# QCW_Bridge_PCBA.net
KiCad netlist of a schematic drawn in Altium Designer
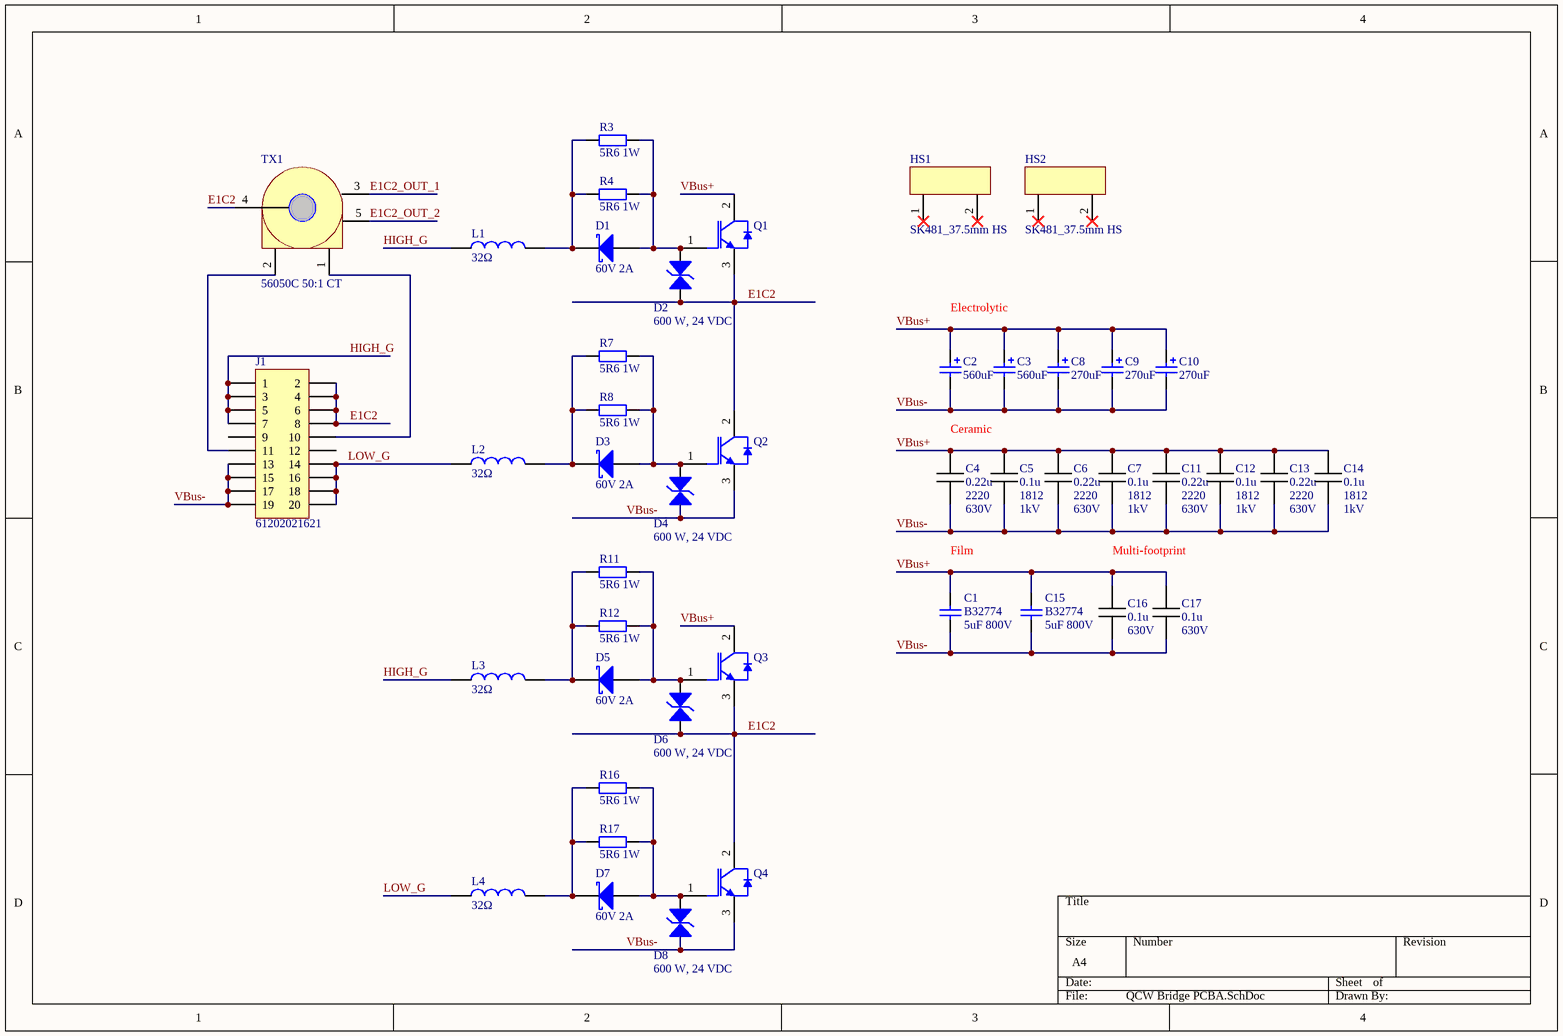
[diagram p0: QCW Bridge PCBA.SchDoc]

(export (version "E")
  (design (tool "Eeschema 10.0.6"))
  (components
    (comp (ref "C1")
      (value "B32774")
      (footprint "B32774 5uF 800V")
      (description "Capacitor")
      (fields (field (name "ALTIUM_VALUE") "5uF 800V") (field (name "PUBLISHER") "Altium Limited"))
      (libsource (lib "Miscellaneous Devices") (part "Cap"))
    )
    (comp (ref "C2")
      (value "560uF")
      (footprint "WCAP-AIL8_35x47")
      (description "WCAP-AIL8 Aluminum Electrolytic Capacitors, 560uF")
      (fields (field (name "PARTNUMBER") "861101486027") (field (name "PUBLISHER") "Wurth Elektronik"))
      (libsource (lib "TV_Altium_library") (part "WCAP-AIL8, 861101486027"))
    )
    (comp (ref "C3")
      (value "560uF")
      (footprint "WCAP-AIL8_35x47")
      (description "WCAP-AIL8 Aluminum Electrolytic Capacitors, 560uF")
      (fields (field (name "PARTNUMBER") "861101486027") (field (name "PUBLISHER") "Wurth Elektronik"))
      (libsource (lib "TV_Altium_library") (part "WCAP-AIL8, 861101486027"))
    )
    (comp (ref "C4")
      (value "Capacitor")
      (footprint "2220C")
      (fields
        (field (name "CAPACITANCE") "0.22u")
        (field (name "PACKAGE") "2220")
        (field (name "VOLTAGE") "630V")
      )
      (libsource (lib "TV_Altium_library") (part "Capacitor"))
    )
    (comp (ref "C5")
      (value "Capacitor")
      (footprint "1812C")
      (fields
        (field (name "CAPACITANCE") "0.1u")
        (field (name "PACKAGE") "1812")
        (field (name "VOLTAGE") "1kV")
      )
      (libsource (lib "TV_Altium_library") (part "Capacitor"))
    )
    (comp (ref "C6")
      (value "Capacitor")
      (footprint "2220C")
      (fields
        (field (name "CAPACITANCE") "0.22u")
        (field (name "PACKAGE") "2220")
        (field (name "VOLTAGE") "630V")
      )
      (libsource (lib "TV_Altium_library") (part "Capacitor"))
    )
    (comp (ref "C7")
      (value "Capacitor")
      (footprint "1812C")
      (fields
        (field (name "CAPACITANCE") "0.1u")
        (field (name "PACKAGE") "1812")
        (field (name "VOLTAGE") "1kV")
      )
      (libsource (lib "TV_Altium_library") (part "Capacitor"))
    )
    (comp (ref "C8")
      (value "270uF")
      (footprint "WCAP-AIL8_25x46")
      (description "WCAP-AIL8 Aluminum Electrolytic Capacitors, 270uF")
      (fields (field (name "PARTNUMBER") "861101484015") (field (name "PUBLISHER") "Wurth Elektronik"))
      (libsource (lib "TV_Altium_library") (part "WCAP-AIL8, 861101484015"))
    )
    (comp (ref "C9")
      (value "270uF")
      (footprint "WCAP-AIL8_25x46")
      (description "WCAP-AIL8 Aluminum Electrolytic Capacitors, 270uF")
      (fields (field (name "PARTNUMBER") "861101484015") (field (name "PUBLISHER") "Wurth Elektronik"))
      (libsource (lib "TV_Altium_library") (part "WCAP-AIL8, 861101484015"))
    )
    (comp (ref "C10")
      (value "270uF")
      (footprint "WCAP-AIL8_25x46")
      (description "WCAP-AIL8 Aluminum Electrolytic Capacitors, 270uF")
      (fields (field (name "PARTNUMBER") "861101484015") (field (name "PUBLISHER") "Wurth Elektronik"))
      (libsource (lib "TV_Altium_library") (part "WCAP-AIL8, 861101484015"))
    )
    (comp (ref "C11")
      (value "Capacitor")
      (footprint "2220C")
      (fields
        (field (name "CAPACITANCE") "0.22u")
        (field (name "PACKAGE") "2220")
        (field (name "VOLTAGE") "630V")
      )
      (libsource (lib "TV_Altium_library") (part "Capacitor"))
    )
    (comp (ref "C12")
      (value "Capacitor")
      (footprint "1812C")
      (fields
        (field (name "CAPACITANCE") "0.1u")
        (field (name "PACKAGE") "1812")
        (field (name "VOLTAGE") "1kV")
      )
      (libsource (lib "TV_Altium_library") (part "Capacitor"))
    )
    (comp (ref "C13")
      (value "Capacitor")
      (footprint "2220C")
      (fields
        (field (name "CAPACITANCE") "0.22u")
        (field (name "PACKAGE") "2220")
        (field (name "VOLTAGE") "630V")
      )
      (libsource (lib "TV_Altium_library") (part "Capacitor"))
    )
    (comp (ref "C14")
      (value "Capacitor")
      (footprint "1812C")
      (fields
        (field (name "CAPACITANCE") "0.1u")
        (field (name "PACKAGE") "1812")
        (field (name "VOLTAGE") "1kV")
      )
      (libsource (lib "TV_Altium_library") (part "Capacitor"))
    )
    (comp (ref "C15")
      (value "B32774")
      (footprint "B32774 5uF 800V")
      (description "Capacitor")
      (fields (field (name "ALTIUM_VALUE") "5uF 800V") (field (name "PUBLISHER") "Altium Limited"))
      (libsource (lib "Miscellaneous Devices") (part "Cap"))
    )
    (comp (ref "C16")
      (value "Capacitor")
      (footprint "Cap_multi_footprint")
      (fields (field (name "CAPACITANCE") "0.1u") (field (name "VOLTAGE") "630V"))
      (libsource (lib "TV_Altium_library") (part "Capacitor"))
    )
    (comp (ref "C17")
      (value "Capacitor")
      (footprint "Cap_multi_footprint")
      (fields (field (name "CAPACITANCE") "0.1u") (field (name "VOLTAGE") "630V"))
      (libsource (lib "TV_Altium_library") (part "Capacitor"))
    )
    (comp (ref "D1")
      (value "60V 2A")
      (footprint "DO-214AA_(SMB-J-BEND)_UNI")
      (description "SS26 Schottky rectifier")
      (libsource (lib "TV_Altium_library") (part "SS26"))
    )
    (comp (ref "D2")
      (value "600 W, 24 VDC")
      (footprint "DO-214AA_Bidirectional")
      (description "WE-TVSP Power TVS Diode, bidirectional, 600 W, 24 VDC")
      (fields
        (field (name "PARTNO") "824521241")
        (field (name "MANUFACTURER") "Wurth Elektronik")
        (field (name "CREATED BY") "Baojun Chen")
      )
      (libsource (lib "TV_Altium_library") (part "WE-TVSP DO-214AA, 824521241"))
    )
    (comp (ref "D3")
      (value "60V 2A")
      (footprint "DO-214AA_(SMB-J-BEND)_UNI")
      (description "SS26 Schottky rectifier")
      (libsource (lib "TV_Altium_library") (part "SS26"))
    )
    (comp (ref "D4")
      (value "600 W, 24 VDC")
      (footprint "DO-214AA_Bidirectional")
      (description "WE-TVSP Power TVS Diode, bidirectional, 600 W, 24 VDC")
      (fields
        (field (name "PARTNO") "824521241")
        (field (name "MANUFACTURER") "Wurth Elektronik")
        (field (name "CREATED BY") "Baojun Chen")
      )
      (libsource (lib "TV_Altium_library") (part "WE-TVSP DO-214AA, 824521241"))
    )
    (comp (ref "D5")
      (value "60V 2A")
      (footprint "DO-214AA_(SMB-J-BEND)_UNI")
      (description "SS26 Schottky rectifier")
      (libsource (lib "TV_Altium_library") (part "SS26"))
    )
    (comp (ref "D6")
      (value "600 W, 24 VDC")
      (footprint "DO-214AA_Bidirectional")
      (description "WE-TVSP Power TVS Diode, bidirectional, 600 W, 24 VDC")
      (fields
        (field (name "PARTNO") "824521241")
        (field (name "MANUFACTURER") "Wurth Elektronik")
        (field (name "CREATED BY") "Baojun Chen")
      )
      (libsource (lib "TV_Altium_library") (part "WE-TVSP DO-214AA, 824521241"))
    )
    (comp (ref "D7")
      (value "60V 2A")
      (footprint "DO-214AA_(SMB-J-BEND)_UNI")
      (description "SS26 Schottky rectifier")
      (libsource (lib "TV_Altium_library") (part "SS26"))
    )
    (comp (ref "D8")
      (value "600 W, 24 VDC")
      (footprint "DO-214AA_Bidirectional")
      (description "WE-TVSP Power TVS Diode, bidirectional, 600 W, 24 VDC")
      (fields
        (field (name "PARTNO") "824521241")
        (field (name "MANUFACTURER") "Wurth Elektronik")
        (field (name "CREATED BY") "Baojun Chen")
      )
      (libsource (lib "TV_Altium_library") (part "WE-TVSP DO-214AA, 824521241"))
    )
    (comp (ref "HS1")
      (value "SK481_37.5mm HS")
      (footprint "SK 481 37.5")
      (libsource (lib "TV_Altium_library") (part "SK_481_37.5"))
    )
    (comp (ref "HS2")
      (value "SK481_37.5mm HS")
      (footprint "SK 481 37.5_FLIP")
      (libsource (lib "TV_Altium_library") (part "SK_481_37.5"))
    )
    (comp (ref "J1")
      (value "61202021621")
      (footprint "61202021621")
      (description "WR-BHD 2.54mm Male Box Header")
      (fields (field (name "MANUFACTURER") "Wurth Elektronik") (field (name "CREATED BY") "Baojun Chen"))
      (libsource (lib "TV_Altium_library") (part "61202021621"))
    )
    (comp (ref "L1")
      (value "32Ω")
      (footprint "WE-CBF_1206_High Speed")
      (description "WE-CBF SMD EMI Suppression Ferrite Bead, 1206, 32Ω")
      (fields (field (name "PARTNUMBER") "7427921") (field (name "PUBLISHER") "Wurth Elektronik"))
      (libsource (lib "TV_Altium_library") (part "WE-CBF, 7427921"))
    )
    (comp (ref "L2")
      (value "32Ω")
      (footprint "WE-CBF_1206_High Speed")
      (description "WE-CBF SMD EMI Suppression Ferrite Bead, 1206, 32Ω")
      (fields (field (name "PARTNUMBER") "7427921") (field (name "PUBLISHER") "Wurth Elektronik"))
      (libsource (lib "TV_Altium_library") (part "WE-CBF, 7427921"))
    )
    (comp (ref "L3")
      (value "32Ω")
      (footprint "WE-CBF_1206_High Speed")
      (description "WE-CBF SMD EMI Suppression Ferrite Bead, 1206, 32Ω")
      (fields (field (name "PARTNUMBER") "7427921") (field (name "PUBLISHER") "Wurth Elektronik"))
      (libsource (lib "TV_Altium_library") (part "WE-CBF, 7427921"))
    )
    (comp (ref "L4")
      (value "32Ω")
      (footprint "WE-CBF_1206_High Speed")
      (description "WE-CBF SMD EMI Suppression Ferrite Bead, 1206, 32Ω")
      (fields (field (name "PARTNUMBER") "7427921") (field (name "PUBLISHER") "Wurth Elektronik"))
      (libsource (lib "TV_Altium_library") (part "WE-CBF, 7427921"))
    )
    (comp (ref "Q1")
      (value "~")
      (footprint "TO-247")
      (description "IGBT, TO-247, Vertical")
      (libsource (lib "TV_Altium_library") (part "TO-247_IGBT_V"))
    )
    (comp (ref "Q2")
      (value "~")
      (footprint "TO-247")
      (description "IGBT, TO-247, Vertical")
      (libsource (lib "TV_Altium_library") (part "TO-247_IGBT_V"))
    )
    (comp (ref "Q3")
      (value "~")
      (footprint "TO-247")
      (description "IGBT, TO-247, Vertical")
      (libsource (lib "TV_Altium_library") (part "TO-247_IGBT_V"))
    )
    (comp (ref "Q4")
      (value "~")
      (footprint "TO-247")
      (description "IGBT, TO-247, Vertical")
      (libsource (lib "TV_Altium_library") (part "TO-247_IGBT_V"))
    )
    (comp (ref "R3")
      (value "5R6 1W")
      (description "Resistor")
      (fields (field (name "Comment") "Res2") (field (name "PUBLISHER") "Altium Limited"))
      (libsource (lib "Miscellaneous Devices") (part "Res2"))
    )
    (comp (ref "R4")
      (value "5R6 1W")
      (description "Resistor")
      (fields (field (name "Comment") "Res2") (field (name "PUBLISHER") "Altium Limited"))
      (libsource (lib "Miscellaneous Devices") (part "Res2"))
    )
    (comp (ref "R7")
      (value "5R6 1W")
      (description "Resistor")
      (fields (field (name "Comment") "Res2") (field (name "PUBLISHER") "Altium Limited"))
      (libsource (lib "Miscellaneous Devices") (part "Res2"))
    )
    (comp (ref "R8")
      (value "5R6 1W")
      (description "Resistor")
      (fields (field (name "Comment") "Res2") (field (name "PUBLISHER") "Altium Limited"))
      (libsource (lib "Miscellaneous Devices") (part "Res2"))
    )
    (comp (ref "R11")
      (value "5R6 1W")
      (description "Resistor")
      (fields (field (name "Comment") "Res2") (field (name "PUBLISHER") "Altium Limited"))
      (libsource (lib "Miscellaneous Devices") (part "Res2"))
    )
    (comp (ref "R12")
      (value "5R6 1W")
      (description "Resistor")
      (fields (field (name "Comment") "Res2") (field (name "PUBLISHER") "Altium Limited"))
      (libsource (lib "Miscellaneous Devices") (part "Res2"))
    )
    (comp (ref "R16")
      (value "5R6 1W")
      (description "Resistor")
      (fields (field (name "Comment") "Res2") (field (name "PUBLISHER") "Altium Limited"))
      (libsource (lib "Miscellaneous Devices") (part "Res2"))
    )
    (comp (ref "R17")
      (value "5R6 1W")
      (description "Resistor")
      (fields (field (name "Comment") "Res2") (field (name "PUBLISHER") "Altium Limited"))
      (libsource (lib "Miscellaneous Devices") (part "Res2"))
    )
    (comp (ref "TX1")
      (value "56050C 50:1 CT")
      (footprint "KMP_5600_ALT")
      (description "Murata 56050C 10A 50:1 CT")
      (libsource (lib "TV_Altium_library") (part "56050C_ALT"))
    )
  )
  (nets
    (net (code "1") (name "/E1C2") (class "Default")
      (node (ref "D2") (pin "2") (pinfunction "2_2") (pintype "passive"))
      (node (ref "D6") (pin "2") (pinfunction "2_2") (pintype "passive"))
      (node (ref "J1") (pin "2") (pinfunction "2_2") (pintype "passive"))
      (node (ref "J1") (pin "4") (pinfunction "4_4") (pintype "passive"))
      (node (ref "J1") (pin "6") (pinfunction "6_6") (pintype "passive"))
      (node (ref "J1") (pin "8") (pinfunction "8_8") (pintype "passive"))
      (node (ref "Q1") (pin "3") (pinfunction "E_3") (pintype "passive"))
      (node (ref "Q2") (pin "2") (pinfunction "C_2") (pintype "passive"))
      (node (ref "Q3") (pin "3") (pinfunction "E_3") (pintype "passive"))
      (node (ref "Q4") (pin "2") (pinfunction "C_2") (pintype "passive"))
      (node (ref "TX1") (pin "4") (pinfunction "4_4") (pintype "passive"))
    )
    (net (code "2") (name "/E1C2_OUT_1") (class "Default")
      (node (ref "TX1") (pin "3") (pinfunction "3_3") (pintype "passive"))
    )
    (net (code "3") (name "/E1C2_OUT_2") (class "Default")
      (node (ref "TX1") (pin "5") (pinfunction "5_5") (pintype "passive"))
    )
    (net (code "4") (name "/HIGH_G") (class "Default")
      (node (ref "J1") (pin "1") (pinfunction "1_1") (pintype "passive"))
      (node (ref "J1") (pin "3") (pinfunction "3_3") (pintype "passive"))
      (node (ref "J1") (pin "5") (pinfunction "5_5") (pintype "passive"))
      (node (ref "J1") (pin "7") (pinfunction "7_7") (pintype "passive"))
      (node (ref "L1") (pin "1") (pinfunction "1_1") (pintype "passive"))
      (node (ref "L3") (pin "1") (pinfunction "1_1") (pintype "passive"))
    )
    (net (code "5") (name "/LOW_G") (class "Default")
      (node (ref "J1") (pin "14") (pinfunction "14_14") (pintype "passive"))
      (node (ref "J1") (pin "16") (pinfunction "16_16") (pintype "passive"))
      (node (ref "J1") (pin "18") (pinfunction "18_18") (pintype "passive"))
      (node (ref "J1") (pin "20") (pinfunction "20_20") (pintype "passive"))
      (node (ref "L2") (pin "1") (pinfunction "1_1") (pintype "passive"))
      (node (ref "L4") (pin "1") (pinfunction "1_1") (pintype "passive"))
    )
    (net (code "6") (name "/VBus+") (class "Default")
      (node (ref "C1") (pin "1") (pinfunction "1_1") (pintype "passive"))
      (node (ref "C10") (pin "1") (pinfunction "P_1") (pintype "passive"))
      (node (ref "C11") (pin "1") (pinfunction "1_1") (pintype "passive"))
      (node (ref "C12") (pin "1") (pinfunction "1_1") (pintype "passive"))
      (node (ref "C13") (pin "1") (pinfunction "1_1") (pintype "passive"))
      (node (ref "C14") (pin "1") (pinfunction "1_1") (pintype "passive"))
      (node (ref "C15") (pin "1") (pinfunction "1_1") (pintype "passive"))
      (node (ref "C16") (pin "1") (pinfunction "1_1") (pintype "passive"))
      (node (ref "C17") (pin "2") (pinfunction "2_2") (pintype "passive"))
      (node (ref "C2") (pin "1") (pinfunction "P_1") (pintype "passive"))
      (node (ref "C3") (pin "1") (pinfunction "P_1") (pintype "passive"))
      (node (ref "C4") (pin "1") (pinfunction "1_1") (pintype "passive"))
      (node (ref "C5") (pin "1") (pinfunction "1_1") (pintype "passive"))
      (node (ref "C6") (pin "1") (pinfunction "1_1") (pintype "passive"))
      (node (ref "C7") (pin "1") (pinfunction "1_1") (pintype "passive"))
      (node (ref "C8") (pin "1") (pinfunction "P_1") (pintype "passive"))
      (node (ref "C9") (pin "1") (pinfunction "P_1") (pintype "passive"))
      (node (ref "Q1") (pin "2") (pinfunction "C_2") (pintype "passive"))
      (node (ref "Q3") (pin "2") (pinfunction "C_2") (pintype "passive"))
    )
    (net (code "7") (name "/VBus-") (class "Default")
      (node (ref "C1") (pin "2") (pinfunction "2_2") (pintype "passive"))
      (node (ref "C10") (pin "2") (pinfunction "N_2") (pintype "passive"))
      (node (ref "C11") (pin "2") (pinfunction "2_2") (pintype "passive"))
      (node (ref "C12") (pin "2") (pinfunction "2_2") (pintype "passive"))
      (node (ref "C13") (pin "2") (pinfunction "2_2") (pintype "passive"))
      (node (ref "C14") (pin "2") (pinfunction "2_2") (pintype "passive"))
      (node (ref "C15") (pin "2") (pinfunction "2_2") (pintype "passive"))
      (node (ref "C16") (pin "2") (pinfunction "2_2") (pintype "passive"))
      (node (ref "C17") (pin "1") (pinfunction "1_1") (pintype "passive"))
      (node (ref "C2") (pin "2") (pinfunction "N_2") (pintype "passive"))
      (node (ref "C3") (pin "2") (pinfunction "N_2") (pintype "passive"))
      (node (ref "C4") (pin "2") (pinfunction "2_2") (pintype "passive"))
      (node (ref "C5") (pin "2") (pinfunction "2_2") (pintype "passive"))
      (node (ref "C6") (pin "2") (pinfunction "2_2") (pintype "passive"))
      (node (ref "C7") (pin "2") (pinfunction "2_2") (pintype "passive"))
      (node (ref "C8") (pin "2") (pinfunction "N_2") (pintype "passive"))
      (node (ref "C9") (pin "2") (pinfunction "N_2") (pintype "passive"))
      (node (ref "D4") (pin "2") (pinfunction "2_2") (pintype "passive"))
      (node (ref "D8") (pin "2") (pinfunction "2_2") (pintype "passive"))
      (node (ref "J1") (pin "13") (pinfunction "13_13") (pintype "passive"))
      (node (ref "J1") (pin "15") (pinfunction "15_15") (pintype "passive"))
      (node (ref "J1") (pin "17") (pinfunction "17_17") (pintype "passive"))
      (node (ref "J1") (pin "19") (pinfunction "19_19") (pintype "passive"))
      (node (ref "Q2") (pin "3") (pinfunction "E_3") (pintype "passive"))
      (node (ref "Q4") (pin "3") (pinfunction "E_3") (pintype "passive"))
    )
    (net (code "8") (name "Net-(D1-PadK)") (class "Default")
      (node (ref "D1") (pin "K") (pinfunction "K_K") (pintype "passive"))
      (node (ref "L1") (pin "2") (pinfunction "2_2") (pintype "passive"))
      (node (ref "R3") (pin "1") (pinfunction "1_1") (pintype "passive"))
      (node (ref "R4") (pin "1") (pinfunction "1_1") (pintype "passive"))
    )
    (net (code "9") (name "Net-(D3-PadK)") (class "Default")
      (node (ref "D3") (pin "K") (pinfunction "K_K") (pintype "passive"))
      (node (ref "L2") (pin "2") (pinfunction "2_2") (pintype "passive"))
      (node (ref "R7") (pin "1") (pinfunction "1_1") (pintype "passive"))
      (node (ref "R8") (pin "1") (pinfunction "1_1") (pintype "passive"))
    )
    (net (code "10") (name "Net-(D5-PadK)") (class "Default")
      (node (ref "D5") (pin "K") (pinfunction "K_K") (pintype "passive"))
      (node (ref "L3") (pin "2") (pinfunction "2_2") (pintype "passive"))
      (node (ref "R11") (pin "1") (pinfunction "1_1") (pintype "passive"))
      (node (ref "R12") (pin "1") (pinfunction "1_1") (pintype "passive"))
    )
    (net (code "11") (name "Net-(D7-PadK)") (class "Default")
      (node (ref "D7") (pin "K") (pinfunction "K_K") (pintype "passive"))
      (node (ref "L4") (pin "2") (pinfunction "2_2") (pintype "passive"))
      (node (ref "R16") (pin "1") (pinfunction "1_1") (pintype "passive"))
      (node (ref "R17") (pin "1") (pinfunction "1_1") (pintype "passive"))
    )
    (net (code "12") (name "Net-(J1-Pad10)") (class "Default")
      (node (ref "J1") (pin "10") (pinfunction "10_10") (pintype "passive"))
      (node (ref "TX1") (pin "1") (pinfunction "1_1") (pintype "passive"))
    )
    (net (code "13") (name "Net-(J1-Pad11)") (class "Default")
      (node (ref "J1") (pin "11") (pinfunction "11_11") (pintype "passive"))
      (node (ref "TX1") (pin "2") (pinfunction "2_2") (pintype "passive"))
    )
    (net (code "14") (name "Net-(Q1-G)") (class "Default")
      (node (ref "D1") (pin "A") (pinfunction "A_A") (pintype "passive"))
      (node (ref "D2") (pin "1") (pinfunction "1_1") (pintype "passive"))
      (node (ref "Q1") (pin "1") (pinfunction "G_1") (pintype "passive"))
      (node (ref "R3") (pin "2") (pinfunction "2_2") (pintype "passive"))
      (node (ref "R4") (pin "2") (pinfunction "2_2") (pintype "passive"))
    )
    (net (code "15") (name "Net-(Q2-G)") (class "Default")
      (node (ref "D3") (pin "A") (pinfunction "A_A") (pintype "passive"))
      (node (ref "D4") (pin "1") (pinfunction "1_1") (pintype "passive"))
      (node (ref "Q2") (pin "1") (pinfunction "G_1") (pintype "passive"))
      (node (ref "R7") (pin "2") (pinfunction "2_2") (pintype "passive"))
      (node (ref "R8") (pin "2") (pinfunction "2_2") (pintype "passive"))
    )
    (net (code "16") (name "Net-(Q3-G)") (class "Default")
      (node (ref "D5") (pin "A") (pinfunction "A_A") (pintype "passive"))
      (node (ref "D6") (pin "1") (pinfunction "1_1") (pintype "passive"))
      (node (ref "Q3") (pin "1") (pinfunction "G_1") (pintype "passive"))
      (node (ref "R11") (pin "2") (pinfunction "2_2") (pintype "passive"))
      (node (ref "R12") (pin "2") (pinfunction "2_2") (pintype "passive"))
    )
    (net (code "17") (name "Net-(Q4-G)") (class "Default")
      (node (ref "D7") (pin "A") (pinfunction "A_A") (pintype "passive"))
      (node (ref "D8") (pin "1") (pinfunction "1_1") (pintype "passive"))
      (node (ref "Q4") (pin "1") (pinfunction "G_1") (pintype "passive"))
      (node (ref "R16") (pin "2") (pinfunction "2_2") (pintype "passive"))
      (node (ref "R17") (pin "2") (pinfunction "2_2") (pintype "passive"))
    )
    (net (code "18") (name "unconnected-(HS1-Pad1)") (class "Default")
      (node (ref "HS1") (pin "1") (pinfunction "1_1") (pintype "passive+no_connect"))
    )
    (net (code "19") (name "unconnected-(HS1-Pad2)") (class "Default")
      (node (ref "HS1") (pin "2") (pinfunction "2_2") (pintype "passive+no_connect"))
    )
    (net (code "20") (name "unconnected-(HS2-Pad1)") (class "Default")
      (node (ref "HS2") (pin "1") (pinfunction "1_1") (pintype "passive+no_connect"))
    )
    (net (code "21") (name "unconnected-(HS2-Pad2)") (class "Default")
      (node (ref "HS2") (pin "2") (pinfunction "2_2") (pintype "passive+no_connect"))
    )
    (net (code "22") (name "unconnected-(J1-Pad9)") (class "Default")
      (node (ref "J1") (pin "9") (pinfunction "9_9") (pintype "passive"))
    )
    (net (code "23") (name "unconnected-(J1-Pad12)") (class "Default")
      (node (ref "J1") (pin "12") (pinfunction "12_12") (pintype "passive"))
    )
  )
)
